# HMI.net
KiCad netlist of a schematic drawn in Altium Designer
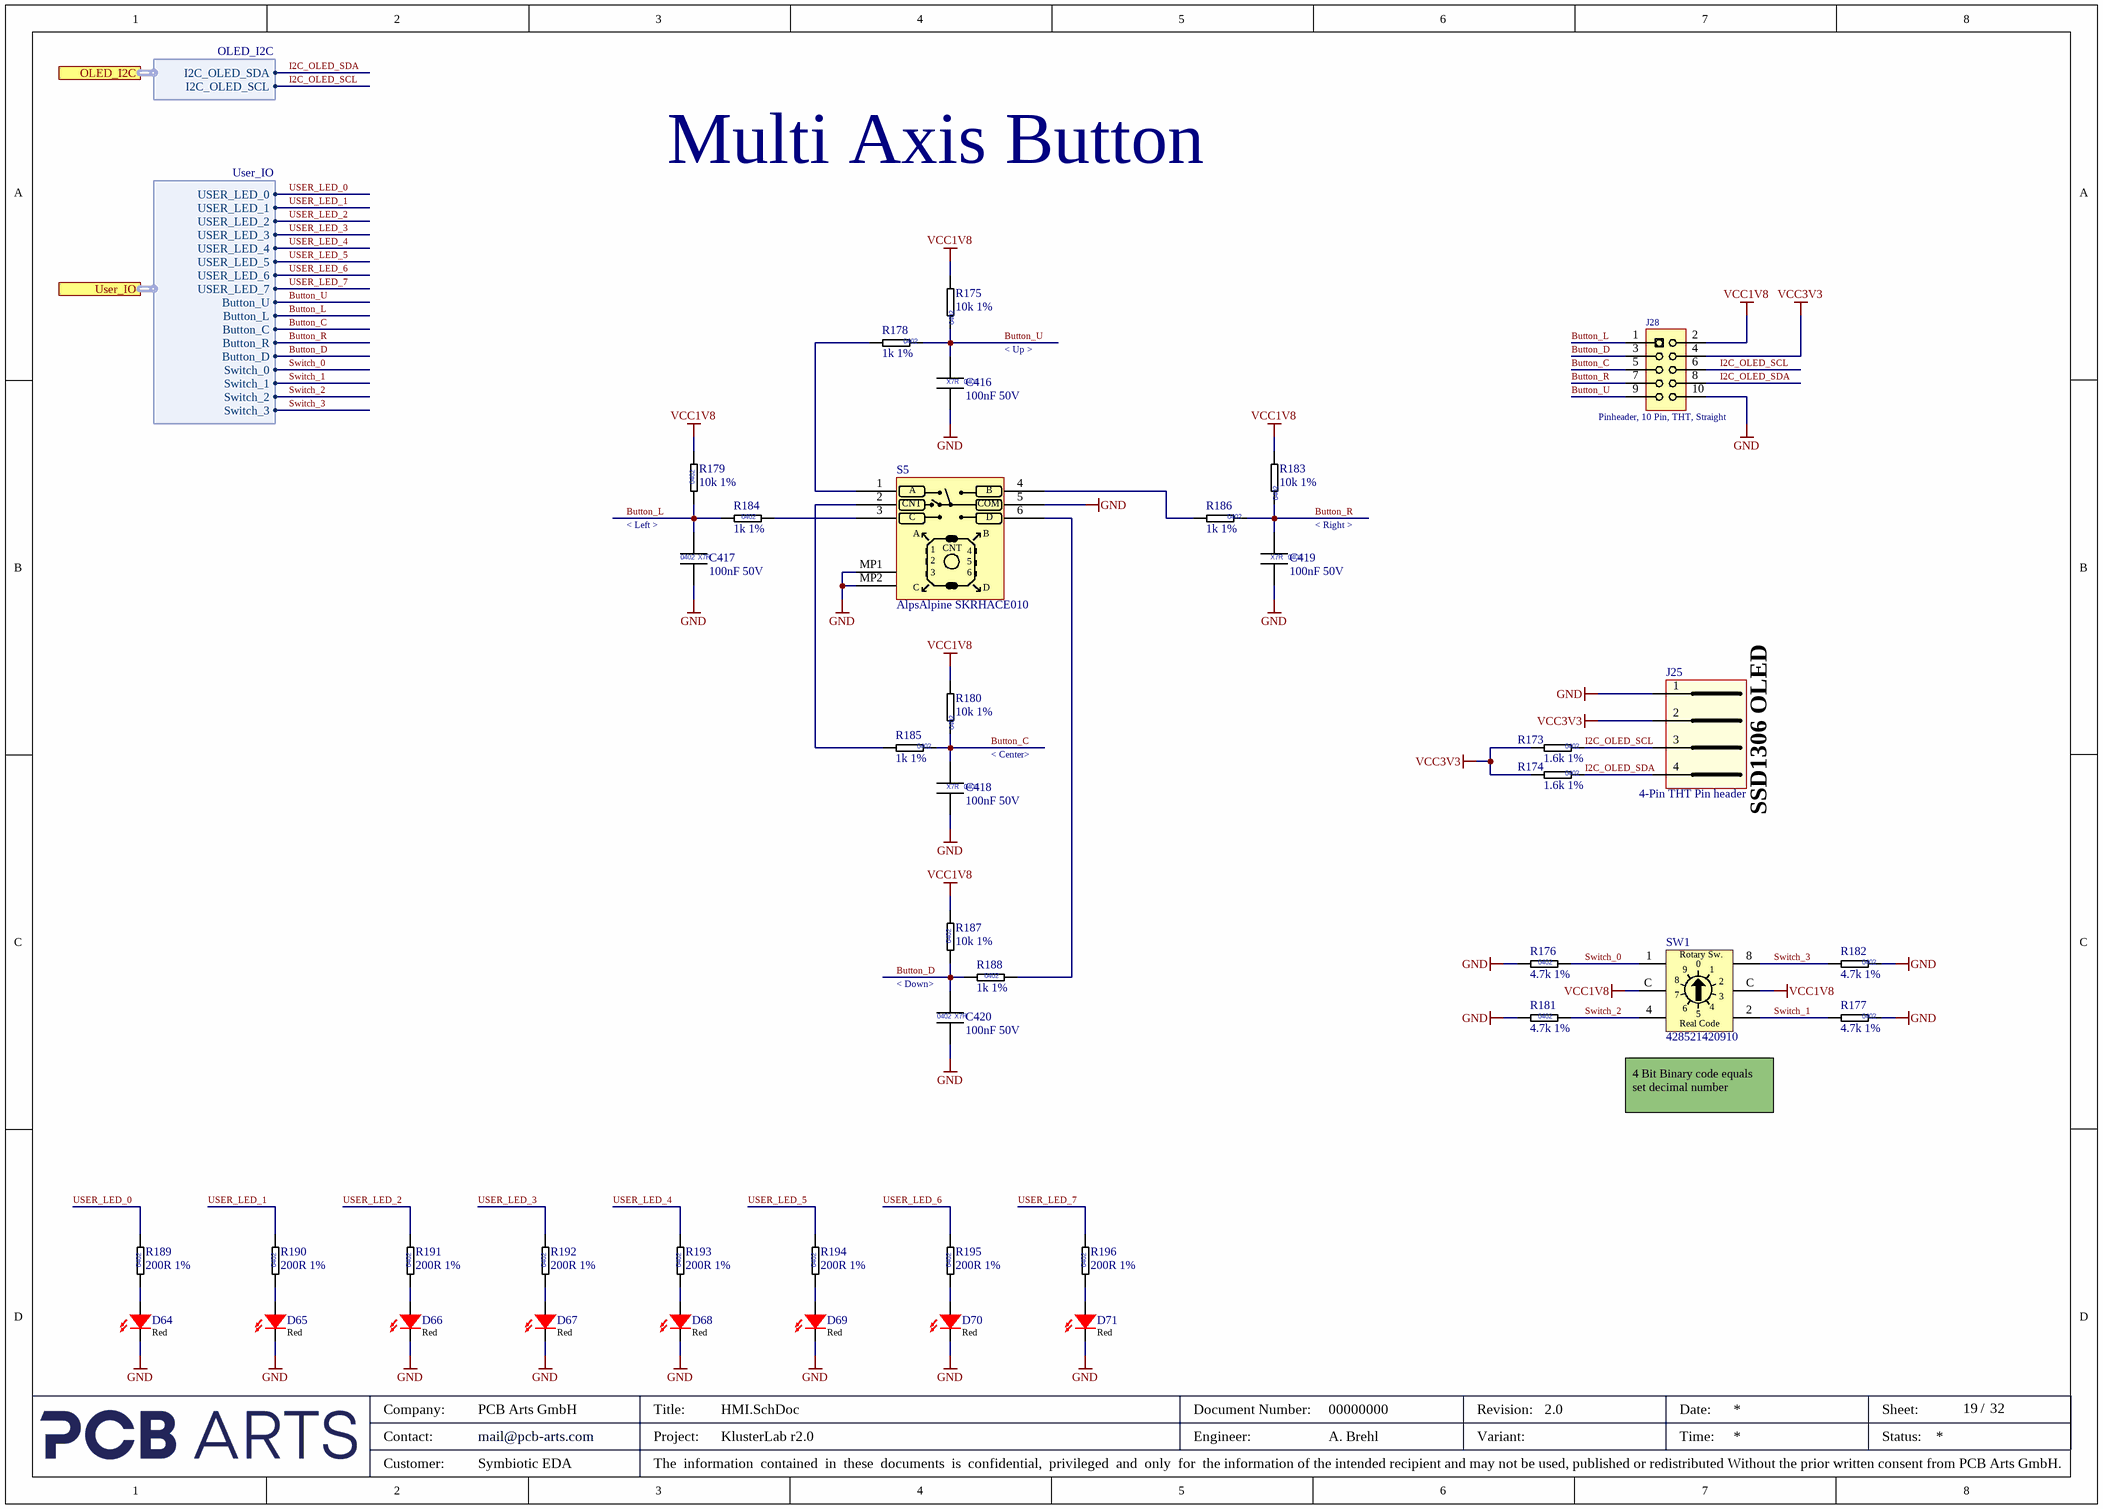
[diagram p0: HMI.SchDoc]

(export (version "E")
  (design (tool "Eeschema 10.0.6"))
  (components
    (comp (ref "C416")
      (value "100nF 50V")
      (footprint "Cap:CAP_0402_L")
      (description "Multilayer Ceramic Capacitors MLCC - SMD/SMT 0402 50VDC")
      (libsource (lib "Cap") (part "CAP_0402_100nF_50V"))
    )
    (comp (ref "C417")
      (value "100nF 50V")
      (footprint "Cap:CAP_0402_L")
      (description "Multilayer Ceramic Capacitors MLCC - SMD/SMT 0402 50VDC")
      (libsource (lib "Cap") (part "CAP_0402_100nF_50V"))
    )
    (comp (ref "C418")
      (value "100nF 50V")
      (footprint "Cap:CAP_0402_L")
      (description "Multilayer Ceramic Capacitors MLCC - SMD/SMT 0402 50VDC")
      (libsource (lib "Cap") (part "CAP_0402_100nF_50V"))
    )
    (comp (ref "C419")
      (value "100nF 50V")
      (footprint "Cap:CAP_0402_L")
      (description "Multilayer Ceramic Capacitors MLCC - SMD/SMT 0402 50VDC")
      (libsource (lib "Cap") (part "CAP_0402_100nF_50V"))
    )
    (comp (ref "C420")
      (value "100nF 50V")
      (footprint "Cap:CAP_0402_L")
      (description "Multilayer Ceramic Capacitors MLCC - SMD/SMT 0402 50VDC")
      (libsource (lib "Cap") (part "CAP_0402_100nF_50V"))
    )
    (comp (ref "D64")
      (value "LTST-S270KRKT")
      (footprint "Active:LED-0603 Sideview")
      (description "RED  0603 Light Emitting Diode")
      (fields (field (name "COLOR") "Red"))
      (libsource (lib "Active") (part "LED 0603 Red Sideview"))
    )
    (comp (ref "D65")
      (value "LTST-S270KRKT")
      (footprint "Active:LED-0603 Sideview")
      (description "RED  0603 Light Emitting Diode")
      (fields (field (name "COLOR") "Red"))
      (libsource (lib "Active") (part "LED 0603 Red Sideview"))
    )
    (comp (ref "D66")
      (value "LTST-S270KRKT")
      (footprint "Active:LED-0603 Sideview")
      (description "RED  0603 Light Emitting Diode")
      (fields (field (name "COLOR") "Red"))
      (libsource (lib "Active") (part "LED 0603 Red Sideview"))
    )
    (comp (ref "D67")
      (value "LTST-S270KRKT")
      (footprint "Active:LED-0603 Sideview")
      (description "RED  0603 Light Emitting Diode")
      (fields (field (name "COLOR") "Red"))
      (libsource (lib "Active") (part "LED 0603 Red Sideview"))
    )
    (comp (ref "D68")
      (value "LTST-S270KRKT")
      (footprint "Active:LED-0603 Sideview")
      (description "RED  0603 Light Emitting Diode")
      (fields (field (name "COLOR") "Red"))
      (libsource (lib "Active") (part "LED 0603 Red Sideview"))
    )
    (comp (ref "D69")
      (value "LTST-S270KRKT")
      (footprint "Active:LED-0603 Sideview")
      (description "RED  0603 Light Emitting Diode")
      (fields (field (name "COLOR") "Red"))
      (libsource (lib "Active") (part "LED 0603 Red Sideview"))
    )
    (comp (ref "D70")
      (value "LTST-S270KRKT")
      (footprint "Active:LED-0603 Sideview")
      (description "RED  0603 Light Emitting Diode")
      (fields (field (name "COLOR") "Red"))
      (libsource (lib "Active") (part "LED 0603 Red Sideview"))
    )
    (comp (ref "D71")
      (value "LTST-S270KRKT")
      (footprint "Active:LED-0603 Sideview")
      (description "RED  0603 Light Emitting Diode")
      (fields (field (name "COLOR") "Red"))
      (libsource (lib "Active") (part "LED 0603 Red Sideview"))
    )
    (comp (ref "J25")
      (value "4-Pin THT Pin header")
      (footprint "Conn:61300411121")
      (description "WR-PHD 2.54mm 4Pin THT Header")
      (libsource (lib "Conn") (part "61300411121_WR-PHD 2.54mm 4Pin THT Header"))
    )
    (comp (ref "J28")
      (value "Pinheader, 10 Pin, THT, Straight")
      (footprint "Conn:62701021621")
      (description "Box Pin header THT 1.27mm 10Pol Straight")
      (libsource (lib "Conn") (part "62701021621_Box Pin header THT 1.27mm 10Pol Straight"))
    )
    (comp (ref "R173")
      (value "1.6k 1%")
      (footprint "Res:RES_0402_L")
      (description "Thick Film Resistors - SMD 1.6kOhm 1%")
      (libsource (lib "Res") (part "RES_0402_1.6k_1%"))
    )
    (comp (ref "R174")
      (value "1.6k 1%")
      (footprint "Res:RES_0402_L")
      (description "Thick Film Resistors - SMD 1.6kOhm 1%")
      (libsource (lib "Res") (part "RES_0402_1.6k_1%"))
    )
    (comp (ref "R175")
      (value "10k 1%")
      (footprint "Res:RES_0402_L")
      (description "Thick Film Resistors - SMD 10kOhm 1%")
      (libsource (lib "Res") (part "RES_0402_10k_1%"))
    )
    (comp (ref "R176")
      (value "4.7k 1%")
      (footprint "Res:RES_0402_L")
      (description "Thick Film Resistors - SMD 4.7kOhm 1%")
      (libsource (lib "Res") (part "RES_0402_4.7k_1%"))
    )
    (comp (ref "R177")
      (value "4.7k 1%")
      (footprint "Res:RES_0402_L")
      (description "Thick Film Resistors - SMD 4.7kOhm 1%")
      (libsource (lib "Res") (part "RES_0402_4.7k_1%"))
    )
    (comp (ref "R178")
      (value "1k 1%")
      (footprint "Res:RES_0402_L")
      (description "Thick Film Resistors - SMD 1kOhm 1%")
      (libsource (lib "Res") (part "RES_0402_1k_1%"))
    )
    (comp (ref "R179")
      (value "10k 1%")
      (footprint "Res:RES_0402_L")
      (description "Thick Film Resistors - SMD 10kOhm 1%")
      (libsource (lib "Res") (part "RES_0402_10k_1%"))
    )
    (comp (ref "R180")
      (value "10k 1%")
      (footprint "Res:RES_0402_L")
      (description "Thick Film Resistors - SMD 10kOhm 1%")
      (libsource (lib "Res") (part "RES_0402_10k_1%"))
    )
    (comp (ref "R181")
      (value "4.7k 1%")
      (footprint "Res:RES_0402_L")
      (description "Thick Film Resistors - SMD 4.7kOhm 1%")
      (libsource (lib "Res") (part "RES_0402_4.7k_1%"))
    )
    (comp (ref "R182")
      (value "4.7k 1%")
      (footprint "Res:RES_0402_L")
      (description "Thick Film Resistors - SMD 4.7kOhm 1%")
      (libsource (lib "Res") (part "RES_0402_4.7k_1%"))
    )
    (comp (ref "R183")
      (value "10k 1%")
      (footprint "Res:RES_0402_L")
      (description "Thick Film Resistors - SMD 10kOhm 1%")
      (libsource (lib "Res") (part "RES_0402_10k_1%"))
    )
    (comp (ref "R184")
      (value "1k 1%")
      (footprint "Res:RES_0402_L")
      (description "Thick Film Resistors - SMD 1kOhm 1%")
      (libsource (lib "Res") (part "RES_0402_1k_1%"))
    )
    (comp (ref "R185")
      (value "1k 1%")
      (footprint "Res:RES_0402_L")
      (description "Thick Film Resistors - SMD 1kOhm 1%")
      (libsource (lib "Res") (part "RES_0402_1k_1%"))
    )
    (comp (ref "R186")
      (value "1k 1%")
      (footprint "Res:RES_0402_L")
      (description "Thick Film Resistors - SMD 1kOhm 1%")
      (libsource (lib "Res") (part "RES_0402_1k_1%"))
    )
    (comp (ref "R187")
      (value "10k 1%")
      (footprint "Res:RES_0402_L")
      (description "Thick Film Resistors - SMD 10kOhm 1%")
      (libsource (lib "Res") (part "RES_0402_10k_1%"))
    )
    (comp (ref "R188")
      (value "1k 1%")
      (footprint "Res:RES_0402_L")
      (description "Thick Film Resistors - SMD 1kOhm 1%")
      (libsource (lib "Res") (part "RES_0402_1k_1%"))
    )
    (comp (ref "R189")
      (value "200R 1%")
      (footprint "Res:RES_0402_L")
      (description "Thick Film Resistors - SMD 200Ohm 1%")
      (libsource (lib "Res") (part "RES_0402_200R 1%"))
    )
    (comp (ref "R190")
      (value "200R 1%")
      (footprint "Res:RES_0402_L")
      (description "Thick Film Resistors - SMD 200Ohm 1%")
      (libsource (lib "Res") (part "RES_0402_200R 1%"))
    )
    (comp (ref "R191")
      (value "200R 1%")
      (footprint "Res:RES_0402_L")
      (description "Thick Film Resistors - SMD 200Ohm 1%")
      (libsource (lib "Res") (part "RES_0402_200R 1%"))
    )
    (comp (ref "R192")
      (value "200R 1%")
      (footprint "Res:RES_0402_L")
      (description "Thick Film Resistors - SMD 200Ohm 1%")
      (libsource (lib "Res") (part "RES_0402_200R 1%"))
    )
    (comp (ref "R193")
      (value "200R 1%")
      (footprint "Res:RES_0402_L")
      (description "Thick Film Resistors - SMD 200Ohm 1%")
      (libsource (lib "Res") (part "RES_0402_200R 1%"))
    )
    (comp (ref "R194")
      (value "200R 1%")
      (footprint "Res:RES_0402_L")
      (description "Thick Film Resistors - SMD 200Ohm 1%")
      (libsource (lib "Res") (part "RES_0402_200R 1%"))
    )
    (comp (ref "R195")
      (value "200R 1%")
      (footprint "Res:RES_0402_L")
      (description "Thick Film Resistors - SMD 200Ohm 1%")
      (libsource (lib "Res") (part "RES_0402_200R 1%"))
    )
    (comp (ref "R196")
      (value "200R 1%")
      (footprint "Res:RES_0402_L")
      (description "Thick Film Resistors - SMD 200Ohm 1%")
      (libsource (lib "Res") (part "RES_0402_200R 1%"))
    )
    (comp (ref "S5")
      (value "AlpsAlpine SKRHACE010")
      (footprint "Electro_Mech:AlpsAlpine_SKRHACE010")
      (description "Multi-Directional Switches, 4-directions, center-push")
      (libsource (lib "Electro_Mech") (part "AlpsAlpine_ SKRHACE010_Multi-Directional-Switches_4-directions_center-push"))
    )
    (comp (ref "SW1")
      (value "428521420910")
      (footprint "Electro_Mech:WÜRTH 428521420910")
      (description "Rotary Switches WS-ROSV IP67 10Pos 2.54mm Lt Grey")
      (libsource (lib "Electro_Mech") (part "428521420910_Rotary Switch WS-ROSV 10Pos Real Code"))
    )
  )
  (nets
    (net (code "3") (name "/Button_C") (class "Default")
      (node (ref "C418") (pin "1") (pinfunction "1_1") (pintype "passive"))
      (node (ref "J28") (pin "5") (pinfunction "5_5") (pintype "passive"))
      (node (ref "R180") (pin "1") (pinfunction "1_1") (pintype "passive"))
      (node (ref "R185") (pin "1") (pinfunction "1_1") (pintype "passive"))
    )
    (net (code "4") (name "/Button_D") (class "Default")
      (node (ref "C420") (pin "1") (pinfunction "1_1") (pintype "passive"))
      (node (ref "J28") (pin "3") (pinfunction "3_3") (pintype "passive"))
      (node (ref "R187") (pin "1") (pinfunction "1_1") (pintype "passive"))
      (node (ref "R188") (pin "1") (pinfunction "1_1") (pintype "passive"))
    )
    (net (code "5") (name "/Button_L") (class "Default")
      (node (ref "C417") (pin "1") (pinfunction "1_1") (pintype "passive"))
      (node (ref "J28") (pin "1") (pinfunction "1_1") (pintype "passive"))
      (node (ref "R179") (pin "1") (pinfunction "1_1") (pintype "passive"))
      (node (ref "R184") (pin "1") (pinfunction "1_1") (pintype "passive"))
    )
    (net (code "6") (name "/Button_R") (class "Default")
      (node (ref "C419") (pin "1") (pinfunction "1_1") (pintype "passive"))
      (node (ref "J28") (pin "7") (pinfunction "7_7") (pintype "passive"))
      (node (ref "R183") (pin "1") (pinfunction "1_1") (pintype "passive"))
      (node (ref "R186") (pin "1") (pinfunction "1_1") (pintype "passive"))
    )
    (net (code "7") (name "/Button_U") (class "Default")
      (node (ref "C416") (pin "1") (pinfunction "1_1") (pintype "passive"))
      (node (ref "J28") (pin "9") (pinfunction "9_9") (pintype "passive"))
      (node (ref "R175") (pin "1") (pinfunction "1_1") (pintype "passive"))
      (node (ref "R178") (pin "1") (pinfunction "1_1") (pintype "passive"))
    )
    (net (code "8") (name "/I2C_OLED_SCL") (class "Default")
      (node (ref "J25") (pin "3") (pinfunction "3_3") (pintype "passive"))
      (node (ref "J28") (pin "6") (pinfunction "6_6") (pintype "passive"))
      (node (ref "R173") (pin "1") (pinfunction "1_1") (pintype "passive"))
    )
    (net (code "9") (name "/I2C_OLED_SDA") (class "Default")
      (node (ref "J25") (pin "4") (pinfunction "4_4") (pintype "passive"))
      (node (ref "J28") (pin "8") (pinfunction "8_8") (pintype "passive"))
      (node (ref "R174") (pin "1") (pinfunction "1_1") (pintype "passive"))
    )
    (net (code "10") (name "/Switch_0") (class "Default")
      (node (ref "R176") (pin "2") (pinfunction "2_2") (pintype "passive"))
      (node (ref "SW1") (pin "1") (pinfunction "1_1") (pintype "passive"))
    )
    (net (code "11") (name "/Switch_1") (class "Default")
      (node (ref "R177") (pin "2") (pinfunction "2_2") (pintype "passive"))
      (node (ref "SW1") (pin "2") (pinfunction "2_2") (pintype "passive"))
    )
    (net (code "12") (name "/Switch_2") (class "Default")
      (node (ref "R181") (pin "2") (pinfunction "2_2") (pintype "passive"))
      (node (ref "SW1") (pin "4") (pinfunction "4_4") (pintype "passive"))
    )
    (net (code "13") (name "/Switch_3") (class "Default")
      (node (ref "R182") (pin "2") (pinfunction "2_2") (pintype "passive"))
      (node (ref "SW1") (pin "8") (pinfunction "8_8") (pintype "passive"))
    )
    (net (code "14") (name "/USER_LED_0") (class "Default")
      (node (ref "R189") (pin "2") (pinfunction "2_2") (pintype "passive"))
    )
    (net (code "15") (name "/USER_LED_1") (class "Default")
      (node (ref "R190") (pin "2") (pinfunction "2_2") (pintype "passive"))
    )
    (net (code "16") (name "/USER_LED_2") (class "Default")
      (node (ref "R191") (pin "2") (pinfunction "2_2") (pintype "passive"))
    )
    (net (code "17") (name "/USER_LED_3") (class "Default")
      (node (ref "R192") (pin "2") (pinfunction "2_2") (pintype "passive"))
    )
    (net (code "18") (name "/USER_LED_4") (class "Default")
      (node (ref "R193") (pin "2") (pinfunction "2_2") (pintype "passive"))
    )
    (net (code "19") (name "/USER_LED_5") (class "Default")
      (node (ref "R194") (pin "2") (pinfunction "2_2") (pintype "passive"))
    )
    (net (code "20") (name "/USER_LED_6") (class "Default")
      (node (ref "R195") (pin "2") (pinfunction "2_2") (pintype "passive"))
    )
    (net (code "21") (name "/USER_LED_7") (class "Default")
      (node (ref "R196") (pin "2") (pinfunction "2_2") (pintype "passive"))
    )
    (net (code "24") (name "GND") (class "Default")
      (node (ref "C416") (pin "2") (pinfunction "2_2") (pintype "passive"))
      (node (ref "C417") (pin "2") (pinfunction "2_2") (pintype "passive"))
      (node (ref "C418") (pin "2") (pinfunction "2_2") (pintype "passive"))
      (node (ref "C419") (pin "2") (pinfunction "2_2") (pintype "passive"))
      (node (ref "C420") (pin "2") (pinfunction "2_2") (pintype "passive"))
      (node (ref "D64") (pin "1") (pinfunction "1_1") (pintype "passive"))
      (node (ref "D65") (pin "1") (pinfunction "1_1") (pintype "passive"))
      (node (ref "D66") (pin "1") (pinfunction "1_1") (pintype "passive"))
      (node (ref "D67") (pin "1") (pinfunction "1_1") (pintype "passive"))
      (node (ref "D68") (pin "1") (pinfunction "1_1") (pintype "passive"))
      (node (ref "D69") (pin "1") (pinfunction "1_1") (pintype "passive"))
      (node (ref "D70") (pin "1") (pinfunction "1_1") (pintype "passive"))
      (node (ref "D71") (pin "1") (pinfunction "1_1") (pintype "passive"))
      (node (ref "J25") (pin "1") (pinfunction "1_1") (pintype "passive"))
      (node (ref "J28") (pin "10") (pinfunction "10_10") (pintype "passive"))
      (node (ref "R176") (pin "1") (pinfunction "1_1") (pintype "passive"))
      (node (ref "R177") (pin "1") (pinfunction "1_1") (pintype "passive"))
      (node (ref "R181") (pin "1") (pinfunction "1_1") (pintype "passive"))
      (node (ref "R182") (pin "1") (pinfunction "1_1") (pintype "passive"))
      (node (ref "S5") (pin "5") (pinfunction "5_5") (pintype "passive"))
      (node (ref "S5") (pin "MP1") (pinfunction "MP1_MP1") (pintype "passive"))
      (node (ref "S5") (pin "MP2") (pinfunction "MP2_MP2") (pintype "passive"))
    )
    (net (code "25") (name "Net-(D64-Pad2)") (class "Default")
      (node (ref "D64") (pin "2") (pinfunction "2_2") (pintype "passive"))
      (node (ref "R189") (pin "1") (pinfunction "1_1") (pintype "passive"))
    )
    (net (code "26") (name "Net-(D65-Pad2)") (class "Default")
      (node (ref "D65") (pin "2") (pinfunction "2_2") (pintype "passive"))
      (node (ref "R190") (pin "1") (pinfunction "1_1") (pintype "passive"))
    )
    (net (code "27") (name "Net-(D66-Pad2)") (class "Default")
      (node (ref "D66") (pin "2") (pinfunction "2_2") (pintype "passive"))
      (node (ref "R191") (pin "1") (pinfunction "1_1") (pintype "passive"))
    )
    (net (code "28") (name "Net-(D67-Pad2)") (class "Default")
      (node (ref "D67") (pin "2") (pinfunction "2_2") (pintype "passive"))
      (node (ref "R192") (pin "1") (pinfunction "1_1") (pintype "passive"))
    )
    (net (code "29") (name "Net-(D68-Pad2)") (class "Default")
      (node (ref "D68") (pin "2") (pinfunction "2_2") (pintype "passive"))
      (node (ref "R193") (pin "1") (pinfunction "1_1") (pintype "passive"))
    )
    (net (code "30") (name "Net-(D69-Pad2)") (class "Default")
      (node (ref "D69") (pin "2") (pinfunction "2_2") (pintype "passive"))
      (node (ref "R194") (pin "1") (pinfunction "1_1") (pintype "passive"))
    )
    (net (code "31") (name "Net-(D70-Pad2)") (class "Default")
      (node (ref "D70") (pin "2") (pinfunction "2_2") (pintype "passive"))
      (node (ref "R195") (pin "1") (pinfunction "1_1") (pintype "passive"))
    )
    (net (code "32") (name "Net-(D71-Pad2)") (class "Default")
      (node (ref "D71") (pin "2") (pinfunction "2_2") (pintype "passive"))
      (node (ref "R196") (pin "1") (pinfunction "1_1") (pintype "passive"))
    )
    (net (code "33") (name "Net-(R178-Pad2)") (class "Default")
      (node (ref "R178") (pin "2") (pinfunction "2_2") (pintype "passive"))
      (node (ref "S5") (pin "1") (pinfunction "1_1") (pintype "passive"))
    )
    (net (code "34") (name "Net-(R184-Pad2)") (class "Default")
      (node (ref "R184") (pin "2") (pinfunction "2_2") (pintype "passive"))
      (node (ref "S5") (pin "3") (pinfunction "3_3") (pintype "passive"))
    )
    (net (code "35") (name "Net-(R185-Pad2)") (class "Default")
      (node (ref "R185") (pin "2") (pinfunction "2_2") (pintype "passive"))
      (node (ref "S5") (pin "2") (pinfunction "2_2") (pintype "passive"))
    )
    (net (code "36") (name "Net-(R186-Pad2)") (class "Default")
      (node (ref "R186") (pin "2") (pinfunction "2_2") (pintype "passive"))
      (node (ref "S5") (pin "4") (pinfunction "4_4") (pintype "passive"))
    )
    (net (code "37") (name "Net-(R188-Pad2)") (class "Default")
      (node (ref "R188") (pin "2") (pinfunction "2_2") (pintype "passive"))
      (node (ref "S5") (pin "6") (pinfunction "6_6") (pintype "passive"))
    )
    (net (code "38") (name "VCC1V8") (class "Default")
      (node (ref "J28") (pin "2") (pinfunction "2_2") (pintype "passive"))
      (node (ref "R175") (pin "2") (pinfunction "2_2") (pintype "passive"))
      (node (ref "R179") (pin "2") (pinfunction "2_2") (pintype "passive"))
      (node (ref "R180") (pin "2") (pinfunction "2_2") (pintype "passive"))
      (node (ref "R183") (pin "2") (pinfunction "2_2") (pintype "passive"))
      (node (ref "R187") (pin "2") (pinfunction "2_2") (pintype "passive"))
      (node (ref "SW1") (pin "C") (pinfunction "C_C") (pintype "passive"))
    )
    (net (code "39") (name "VCC3V3") (class "Default")
      (node (ref "J25") (pin "2") (pinfunction "2_2") (pintype "passive"))
      (node (ref "J28") (pin "4") (pinfunction "4_4") (pintype "passive"))
      (node (ref "R173") (pin "2") (pinfunction "2_2") (pintype "passive"))
      (node (ref "R174") (pin "2") (pinfunction "2_2") (pintype "passive"))
    )
  )
)
